# BatteryBalancingRev3.net
KiCad netlist of a schematic drawn in Altium Designer
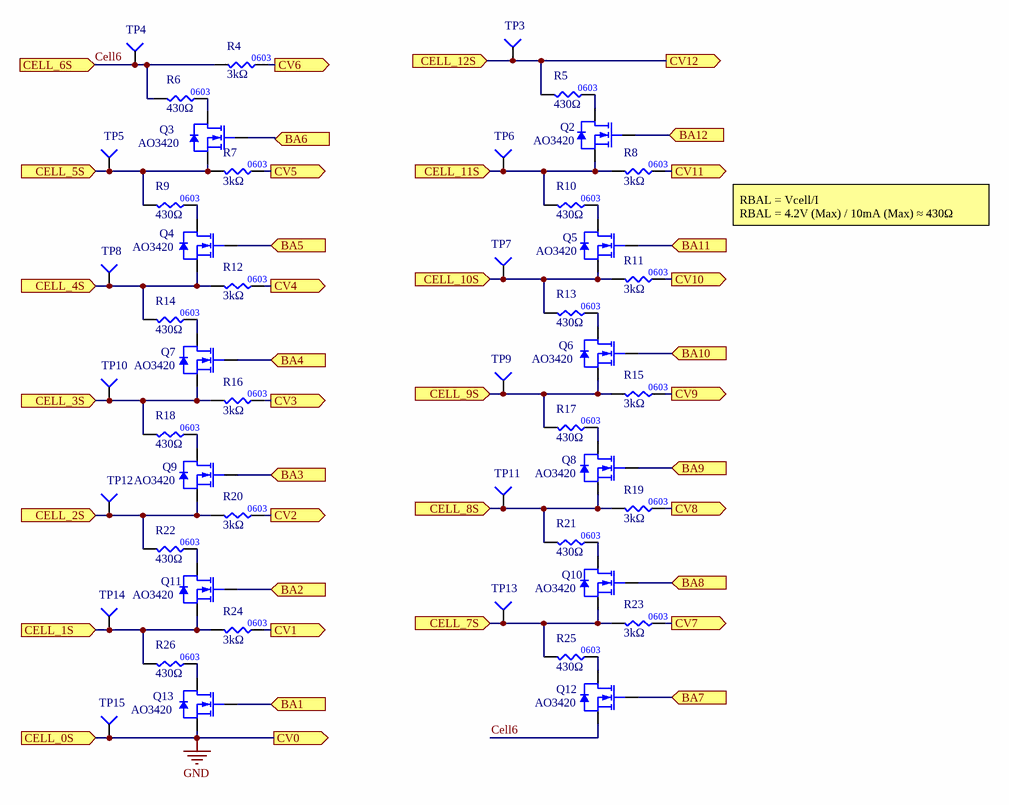
[diagram p0: BatteryBalancingRev3.SchDoc]

(export (version "E")
  (design (tool "Eeschema 10.0.6"))
  (components
    (comp (ref "Q2")
      (value "NMOS_20V_6A")
      (footprint "SOT23-3")
      (description "MOSFET N-CH 20V 6A SOT-23")
      (fields (field (name "MANUFACTURER PART NUMBER 1") "AO3420"))
      (libsource (lib "UWRT_Schematic_Library_2020") (part "NMOS_20V_6A"))
    )
    (comp (ref "Q3")
      (value "NMOS_20V_6A")
      (footprint "SOT23-3")
      (description "MOSFET N-CH 20V 6A SOT-23")
      (fields (field (name "MANUFACTURER PART NUMBER 1") "AO3420"))
      (libsource (lib "UWRT_Schematic_Library_2020") (part "NMOS_20V_6A"))
    )
    (comp (ref "Q4")
      (value "NMOS_20V_6A")
      (footprint "SOT23-3")
      (description "MOSFET N-CH 20V 6A SOT-23")
      (fields (field (name "MANUFACTURER PART NUMBER 1") "AO3420"))
      (libsource (lib "UWRT_Schematic_Library_2020") (part "NMOS_20V_6A"))
    )
    (comp (ref "Q5")
      (value "NMOS_20V_6A")
      (footprint "SOT23-3")
      (description "MOSFET N-CH 20V 6A SOT-23")
      (fields (field (name "MANUFACTURER PART NUMBER 1") "AO3420"))
      (libsource (lib "UWRT_Schematic_Library_2020") (part "NMOS_20V_6A"))
    )
    (comp (ref "Q6")
      (value "NMOS_20V_6A")
      (footprint "SOT23-3")
      (description "MOSFET N-CH 20V 6A SOT-23")
      (fields (field (name "MANUFACTURER PART NUMBER 1") "AO3420"))
      (libsource (lib "UWRT_Schematic_Library_2020") (part "NMOS_20V_6A"))
    )
    (comp (ref "Q7")
      (value "NMOS_20V_6A")
      (footprint "SOT23-3")
      (description "MOSFET N-CH 20V 6A SOT-23")
      (fields (field (name "MANUFACTURER PART NUMBER 1") "AO3420"))
      (libsource (lib "UWRT_Schematic_Library_2020") (part "NMOS_20V_6A"))
    )
    (comp (ref "Q8")
      (value "NMOS_20V_6A")
      (footprint "SOT23-3")
      (description "MOSFET N-CH 20V 6A SOT-23")
      (fields (field (name "MANUFACTURER PART NUMBER 1") "AO3420"))
      (libsource (lib "UWRT_Schematic_Library_2020") (part "NMOS_20V_6A"))
    )
    (comp (ref "Q9")
      (value "NMOS_20V_6A")
      (footprint "SOT23-3")
      (description "MOSFET N-CH 20V 6A SOT-23")
      (fields (field (name "MANUFACTURER PART NUMBER 1") "AO3420"))
      (libsource (lib "UWRT_Schematic_Library_2020") (part "NMOS_20V_6A"))
    )
    (comp (ref "Q10")
      (value "NMOS_20V_6A")
      (footprint "SOT23-3")
      (description "MOSFET N-CH 20V 6A SOT-23")
      (fields (field (name "MANUFACTURER PART NUMBER 1") "AO3420"))
      (libsource (lib "UWRT_Schematic_Library_2020") (part "NMOS_20V_6A"))
    )
    (comp (ref "Q11")
      (value "NMOS_20V_6A")
      (footprint "SOT23-3")
      (description "MOSFET N-CH 20V 6A SOT-23")
      (fields (field (name "MANUFACTURER PART NUMBER 1") "AO3420"))
      (libsource (lib "UWRT_Schematic_Library_2020") (part "NMOS_20V_6A"))
    )
    (comp (ref "Q12")
      (value "NMOS_20V_6A")
      (footprint "SOT23-3")
      (description "MOSFET N-CH 20V 6A SOT-23")
      (fields (field (name "MANUFACTURER PART NUMBER 1") "AO3420"))
      (libsource (lib "UWRT_Schematic_Library_2020") (part "NMOS_20V_6A"))
    )
    (comp (ref "Q13")
      (value "NMOS_20V_6A")
      (footprint "SOT23-3")
      (description "MOSFET N-CH 20V 6A SOT-23")
      (fields (field (name "MANUFACTURER PART NUMBER 1") "AO3420"))
      (libsource (lib "UWRT_Schematic_Library_2020") (part "NMOS_20V_6A"))
    )
    (comp (ref "R4")
      (value "3kΩ")
      (footprint "RES0603")
      (description "RES 3K OHM 1% 1/10W 0603")
      (fields (field (name "Comment") "RES_3kΩ_0603_1%"))
      (libsource (lib "UWRT_Schematic_Library_2020") (part "RES_3kΩ_0603_1%"))
    )
    (comp (ref "R5")
      (value "430Ω")
      (footprint "RES0603")
      (description "RES 430 OHM 5% 1/10W 0603")
      (fields (field (name "Comment") "RES_430Ω_0603_5%"))
      (libsource (lib "UWRT_Schematic_Library_2020") (part "RES_430Ω_0603_5%"))
    )
    (comp (ref "R6")
      (value "430Ω")
      (footprint "RES0603")
      (description "RES 430 OHM 5% 1/10W 0603")
      (fields (field (name "Comment") "RES_430Ω_0603_5%"))
      (libsource (lib "UWRT_Schematic_Library_2020") (part "RES_430Ω_0603_5%"))
    )
    (comp (ref "R7")
      (value "3kΩ")
      (footprint "RES0603")
      (description "RES 3K OHM 1% 1/10W 0603")
      (fields (field (name "Comment") "RES_3kΩ_0603_1%"))
      (libsource (lib "UWRT_Schematic_Library_2020") (part "RES_3kΩ_0603_1%"))
    )
    (comp (ref "R8")
      (value "3kΩ")
      (footprint "RES0603")
      (description "RES 3K OHM 1% 1/10W 0603")
      (fields (field (name "Comment") "RES_3kΩ_0603_1%"))
      (libsource (lib "UWRT_Schematic_Library_2020") (part "RES_3kΩ_0603_1%"))
    )
    (comp (ref "R9")
      (value "430Ω")
      (footprint "RES0603")
      (description "RES 430 OHM 5% 1/10W 0603")
      (fields (field (name "Comment") "RES_430Ω_0603_5%"))
      (libsource (lib "UWRT_Schematic_Library_2020") (part "RES_430Ω_0603_5%"))
    )
    (comp (ref "R10")
      (value "430Ω")
      (footprint "RES0603")
      (description "RES 430 OHM 5% 1/10W 0603")
      (fields (field (name "Comment") "RES_430Ω_0603_5%"))
      (libsource (lib "UWRT_Schematic_Library_2020") (part "RES_430Ω_0603_5%"))
    )
    (comp (ref "R11")
      (value "3kΩ")
      (footprint "RES0603")
      (description "RES 3K OHM 1% 1/10W 0603")
      (fields (field (name "Comment") "RES_3kΩ_0603_1%"))
      (libsource (lib "UWRT_Schematic_Library_2020") (part "RES_3kΩ_0603_1%"))
    )
    (comp (ref "R12")
      (value "3kΩ")
      (footprint "RES0603")
      (description "RES 3K OHM 1% 1/10W 0603")
      (fields (field (name "Comment") "RES_3kΩ_0603_1%"))
      (libsource (lib "UWRT_Schematic_Library_2020") (part "RES_3kΩ_0603_1%"))
    )
    (comp (ref "R13")
      (value "430Ω")
      (footprint "RES0603")
      (description "RES 430 OHM 5% 1/10W 0603")
      (fields (field (name "Comment") "RES_430Ω_0603_5%"))
      (libsource (lib "UWRT_Schematic_Library_2020") (part "RES_430Ω_0603_5%"))
    )
    (comp (ref "R14")
      (value "430Ω")
      (footprint "RES0603")
      (description "RES 430 OHM 5% 1/10W 0603")
      (fields (field (name "Comment") "RES_430Ω_0603_5%"))
      (libsource (lib "UWRT_Schematic_Library_2020") (part "RES_430Ω_0603_5%"))
    )
    (comp (ref "R15")
      (value "3kΩ")
      (footprint "RES0603")
      (description "RES 3K OHM 1% 1/10W 0603")
      (fields (field (name "Comment") "RES_3kΩ_0603_1%"))
      (libsource (lib "UWRT_Schematic_Library_2020") (part "RES_3kΩ_0603_1%"))
    )
    (comp (ref "R16")
      (value "3kΩ")
      (footprint "RES0603")
      (description "RES 3K OHM 1% 1/10W 0603")
      (fields (field (name "Comment") "RES_3kΩ_0603_1%"))
      (libsource (lib "UWRT_Schematic_Library_2020") (part "RES_3kΩ_0603_1%"))
    )
    (comp (ref "R17")
      (value "430Ω")
      (footprint "RES0603")
      (description "RES 430 OHM 5% 1/10W 0603")
      (fields (field (name "Comment") "RES_430Ω_0603_5%"))
      (libsource (lib "UWRT_Schematic_Library_2020") (part "RES_430Ω_0603_5%"))
    )
    (comp (ref "R18")
      (value "430Ω")
      (footprint "RES0603")
      (description "RES 430 OHM 5% 1/10W 0603")
      (fields (field (name "Comment") "RES_430Ω_0603_5%"))
      (libsource (lib "UWRT_Schematic_Library_2020") (part "RES_430Ω_0603_5%"))
    )
    (comp (ref "R19")
      (value "3kΩ")
      (footprint "RES0603")
      (description "RES 3K OHM 1% 1/10W 0603")
      (fields (field (name "Comment") "RES_3kΩ_0603_1%"))
      (libsource (lib "UWRT_Schematic_Library_2020") (part "RES_3kΩ_0603_1%"))
    )
    (comp (ref "R20")
      (value "3kΩ")
      (footprint "RES0603")
      (description "RES 3K OHM 1% 1/10W 0603")
      (fields (field (name "Comment") "RES_3kΩ_0603_1%"))
      (libsource (lib "UWRT_Schematic_Library_2020") (part "RES_3kΩ_0603_1%"))
    )
    (comp (ref "R21")
      (value "430Ω")
      (footprint "RES0603")
      (description "RES 430 OHM 5% 1/10W 0603")
      (fields (field (name "Comment") "RES_430Ω_0603_5%"))
      (libsource (lib "UWRT_Schematic_Library_2020") (part "RES_430Ω_0603_5%"))
    )
    (comp (ref "R22")
      (value "430Ω")
      (footprint "RES0603")
      (description "RES 430 OHM 5% 1/10W 0603")
      (fields (field (name "Comment") "RES_430Ω_0603_5%"))
      (libsource (lib "UWRT_Schematic_Library_2020") (part "RES_430Ω_0603_5%"))
    )
    (comp (ref "R23")
      (value "3kΩ")
      (footprint "RES0603")
      (description "RES 3K OHM 1% 1/10W 0603")
      (fields (field (name "Comment") "RES_3kΩ_0603_1%"))
      (libsource (lib "UWRT_Schematic_Library_2020") (part "RES_3kΩ_0603_1%"))
    )
    (comp (ref "R24")
      (value "3kΩ")
      (footprint "RES0603")
      (description "RES 3K OHM 1% 1/10W 0603")
      (fields (field (name "Comment") "RES_3kΩ_0603_1%"))
      (libsource (lib "UWRT_Schematic_Library_2020") (part "RES_3kΩ_0603_1%"))
    )
    (comp (ref "R25")
      (value "430Ω")
      (footprint "RES0603")
      (description "RES 430 OHM 5% 1/10W 0603")
      (fields (field (name "Comment") "RES_430Ω_0603_5%"))
      (libsource (lib "UWRT_Schematic_Library_2020") (part "RES_430Ω_0603_5%"))
    )
    (comp (ref "R26")
      (value "430Ω")
      (footprint "RES0603")
      (description "RES 430 OHM 5% 1/10W 0603")
      (fields (field (name "Comment") "RES_430Ω_0603_5%"))
      (libsource (lib "UWRT_Schematic_Library_2020") (part "RES_430Ω_0603_5%"))
    )
    (comp (ref "TP3")
      (value "TESTPOINT_1MM_SQUARE")
      (footprint "TESTPOINT_SQUARE_1MM")
      (description "CELL6")
      (libsource (lib "UWRT_Schematic_Library_2020") (part "TESTPOINT_1MM_SQUARE"))
    )
    (comp (ref "TP4")
      (value "TESTPOINT_1MM_SQUARE")
      (footprint "TESTPOINT_SQUARE_1MM")
      (description "CELL11")
      (libsource (lib "UWRT_Schematic_Library_2020") (part "TESTPOINT_1MM_SQUARE"))
    )
    (comp (ref "TP5")
      (value "TESTPOINT_1MM_SQUARE")
      (footprint "TESTPOINT_SQUARE_1MM")
      (description "CELL5")
      (libsource (lib "UWRT_Schematic_Library_2020") (part "TESTPOINT_1MM_SQUARE"))
    )
    (comp (ref "TP6")
      (value "TESTPOINT_1MM_SQUARE")
      (footprint "TESTPOINT_SQUARE_1MM")
      (description "CELL11")
      (libsource (lib "UWRT_Schematic_Library_2020") (part "TESTPOINT_1MM_SQUARE"))
    )
    (comp (ref "TP7")
      (value "TESTPOINT_1MM_SQUARE")
      (footprint "TESTPOINT_SQUARE_1MM")
      (description "CELL10")
      (libsource (lib "UWRT_Schematic_Library_2020") (part "TESTPOINT_1MM_SQUARE"))
    )
    (comp (ref "TP8")
      (value "TESTPOINT_1MM_SQUARE")
      (footprint "TESTPOINT_SQUARE_1MM")
      (description "CELL4")
      (libsource (lib "UWRT_Schematic_Library_2020") (part "TESTPOINT_1MM_SQUARE"))
    )
    (comp (ref "TP9")
      (value "TESTPOINT_1MM_SQUARE")
      (footprint "TESTPOINT_SQUARE_1MM")
      (description "CELL9")
      (libsource (lib "UWRT_Schematic_Library_2020") (part "TESTPOINT_1MM_SQUARE"))
    )
    (comp (ref "TP10")
      (value "TESTPOINT_1MM_SQUARE")
      (footprint "TESTPOINT_SQUARE_1MM")
      (description "CELL3")
      (libsource (lib "UWRT_Schematic_Library_2020") (part "TESTPOINT_1MM_SQUARE"))
    )
    (comp (ref "TP11")
      (value "TESTPOINT_1MM_SQUARE")
      (footprint "TESTPOINT_SQUARE_1MM")
      (description "CELL8")
      (libsource (lib "UWRT_Schematic_Library_2020") (part "TESTPOINT_1MM_SQUARE"))
    )
    (comp (ref "TP12")
      (value "TESTPOINT_1MM_SQUARE")
      (footprint "TESTPOINT_SQUARE_1MM")
      (description "CELL2")
      (libsource (lib "UWRT_Schematic_Library_2020") (part "TESTPOINT_1MM_SQUARE"))
    )
    (comp (ref "TP13")
      (value "TESTPOINT_1MM_SQUARE")
      (footprint "TESTPOINT_SQUARE_1MM")
      (description "CELL7")
      (libsource (lib "UWRT_Schematic_Library_2020") (part "TESTPOINT_1MM_SQUARE"))
    )
    (comp (ref "TP14")
      (value "TESTPOINT_1MM_SQUARE")
      (footprint "TESTPOINT_SQUARE_1MM")
      (description "CELL1")
      (libsource (lib "UWRT_Schematic_Library_2020") (part "TESTPOINT_1MM_SQUARE"))
    )
    (comp (ref "TP15")
      (value "TESTPOINT_1MM_SQUARE")
      (footprint "TESTPOINT_SQUARE_1MM")
      (description "CELL0")
      (libsource (lib "UWRT_Schematic_Library_2020") (part "TESTPOINT_1MM_SQUARE"))
    )
  )
  (nets
    (net (code "1") (name "/BA1") (class "Default")
      (node (ref "Q13") (pin "1") (pinfunction "GATE_1") (pintype "passive"))
    )
    (net (code "2") (name "/BA2") (class "Default")
      (node (ref "Q11") (pin "1") (pinfunction "GATE_1") (pintype "passive"))
    )
    (net (code "3") (name "/BA3") (class "Default")
      (node (ref "Q9") (pin "1") (pinfunction "GATE_1") (pintype "passive"))
    )
    (net (code "4") (name "/BA4") (class "Default")
      (node (ref "Q7") (pin "1") (pinfunction "GATE_1") (pintype "passive"))
    )
    (net (code "5") (name "/BA5") (class "Default")
      (node (ref "Q4") (pin "1") (pinfunction "GATE_1") (pintype "passive"))
    )
    (net (code "6") (name "/BA6") (class "Default")
      (node (ref "Q3") (pin "1") (pinfunction "GATE_1") (pintype "passive"))
    )
    (net (code "7") (name "/BA7") (class "Default")
      (node (ref "Q12") (pin "1") (pinfunction "GATE_1") (pintype "passive"))
    )
    (net (code "8") (name "/BA8") (class "Default")
      (node (ref "Q10") (pin "1") (pinfunction "GATE_1") (pintype "passive"))
    )
    (net (code "9") (name "/BA9") (class "Default")
      (node (ref "Q8") (pin "1") (pinfunction "GATE_1") (pintype "passive"))
    )
    (net (code "10") (name "/BA10") (class "Default")
      (node (ref "Q6") (pin "1") (pinfunction "GATE_1") (pintype "passive"))
    )
    (net (code "11") (name "/BA11") (class "Default")
      (node (ref "Q5") (pin "1") (pinfunction "GATE_1") (pintype "passive"))
    )
    (net (code "12") (name "/BA12") (class "Default")
      (node (ref "Q2") (pin "1") (pinfunction "GATE_1") (pintype "passive"))
    )
    (net (code "13") (name "/CELL_1S") (class "Default")
      (node (ref "Q11") (pin "2") (pinfunction "SOURCE_2") (pintype "passive"))
      (node (ref "R24") (pin "1") (pinfunction "1_1") (pintype "passive"))
      (node (ref "R26") (pin "1") (pinfunction "1_1") (pintype "passive"))
      (node (ref "TP14") (pin "1") (pinfunction "=value_1") (pintype "passive"))
    )
    (net (code "14") (name "/CELL_2S") (class "Default")
      (node (ref "Q9") (pin "2") (pinfunction "SOURCE_2") (pintype "passive"))
      (node (ref "R20") (pin "1") (pinfunction "1_1") (pintype "passive"))
      (node (ref "R22") (pin "1") (pinfunction "1_1") (pintype "passive"))
      (node (ref "TP12") (pin "1") (pinfunction "=value_1") (pintype "passive"))
    )
    (net (code "15") (name "/CELL_3S") (class "Default")
      (node (ref "Q7") (pin "2") (pinfunction "SOURCE_2") (pintype "passive"))
      (node (ref "R16") (pin "1") (pinfunction "1_1") (pintype "passive"))
      (node (ref "R18") (pin "1") (pinfunction "1_1") (pintype "passive"))
      (node (ref "TP10") (pin "1") (pinfunction "=value_1") (pintype "passive"))
    )
    (net (code "16") (name "/CELL_4S") (class "Default")
      (node (ref "Q4") (pin "2") (pinfunction "SOURCE_2") (pintype "passive"))
      (node (ref "R12") (pin "1") (pinfunction "1_1") (pintype "passive"))
      (node (ref "R14") (pin "1") (pinfunction "1_1") (pintype "passive"))
      (node (ref "TP8") (pin "1") (pinfunction "=value_1") (pintype "passive"))
    )
    (net (code "17") (name "/CELL_5S") (class "Default")
      (node (ref "Q3") (pin "2") (pinfunction "SOURCE_2") (pintype "passive"))
      (node (ref "R7") (pin "1") (pinfunction "1_1") (pintype "passive"))
      (node (ref "R9") (pin "1") (pinfunction "1_1") (pintype "passive"))
      (node (ref "TP5") (pin "1") (pinfunction "=value_1") (pintype "passive"))
    )
    (net (code "18") (name "/CELL_7S") (class "Default")
      (node (ref "Q10") (pin "2") (pinfunction "SOURCE_2") (pintype "passive"))
      (node (ref "R23") (pin "1") (pinfunction "1_1") (pintype "passive"))
      (node (ref "R25") (pin "1") (pinfunction "1_1") (pintype "passive"))
      (node (ref "TP13") (pin "1") (pinfunction "=value_1") (pintype "passive"))
    )
    (net (code "19") (name "/CELL_8S") (class "Default")
      (node (ref "Q8") (pin "2") (pinfunction "SOURCE_2") (pintype "passive"))
      (node (ref "R19") (pin "1") (pinfunction "1_1") (pintype "passive"))
      (node (ref "R21") (pin "1") (pinfunction "1_1") (pintype "passive"))
      (node (ref "TP11") (pin "1") (pinfunction "=value_1") (pintype "passive"))
    )
    (net (code "20") (name "/CELL_9S") (class "Default")
      (node (ref "Q6") (pin "2") (pinfunction "SOURCE_2") (pintype "passive"))
      (node (ref "R15") (pin "1") (pinfunction "1_1") (pintype "passive"))
      (node (ref "R17") (pin "1") (pinfunction "1_1") (pintype "passive"))
      (node (ref "TP9") (pin "1") (pinfunction "=value_1") (pintype "passive"))
    )
    (net (code "21") (name "/CELL_10S") (class "Default")
      (node (ref "Q5") (pin "2") (pinfunction "SOURCE_2") (pintype "passive"))
      (node (ref "R11") (pin "1") (pinfunction "1_1") (pintype "passive"))
      (node (ref "R13") (pin "1") (pinfunction "1_1") (pintype "passive"))
      (node (ref "TP7") (pin "1") (pinfunction "=value_1") (pintype "passive"))
    )
    (net (code "22") (name "/CELL_11S") (class "Default")
      (node (ref "Q2") (pin "2") (pinfunction "SOURCE_2") (pintype "passive"))
      (node (ref "R10") (pin "1") (pinfunction "1_1") (pintype "passive"))
      (node (ref "R8") (pin "1") (pinfunction "1_1") (pintype "passive"))
      (node (ref "TP6") (pin "1") (pinfunction "=value_1") (pintype "passive"))
    )
    (net (code "23") (name "/CELL_12S") (class "Default")
      (node (ref "R5") (pin "1") (pinfunction "1_1") (pintype "passive"))
      (node (ref "TP3") (pin "1") (pinfunction "=value_1") (pintype "passive"))
    )
    (net (code "24") (name "/CV1") (class "Default")
      (node (ref "R24") (pin "2") (pinfunction "2_2") (pintype "passive"))
    )
    (net (code "25") (name "/CV2") (class "Default")
      (node (ref "R20") (pin "2") (pinfunction "2_2") (pintype "passive"))
    )
    (net (code "26") (name "/CV3") (class "Default")
      (node (ref "R16") (pin "2") (pinfunction "2_2") (pintype "passive"))
    )
    (net (code "27") (name "/CV4") (class "Default")
      (node (ref "R12") (pin "2") (pinfunction "2_2") (pintype "passive"))
    )
    (net (code "28") (name "/CV5") (class "Default")
      (node (ref "R7") (pin "2") (pinfunction "2_2") (pintype "passive"))
    )
    (net (code "29") (name "/CV6") (class "Default")
      (node (ref "R4") (pin "2") (pinfunction "2_2") (pintype "passive"))
    )
    (net (code "30") (name "/CV7") (class "Default")
      (node (ref "R23") (pin "2") (pinfunction "2_2") (pintype "passive"))
    )
    (net (code "31") (name "/CV8") (class "Default")
      (node (ref "R19") (pin "2") (pinfunction "2_2") (pintype "passive"))
    )
    (net (code "32") (name "/CV9") (class "Default")
      (node (ref "R15") (pin "2") (pinfunction "2_2") (pintype "passive"))
    )
    (net (code "33") (name "/CV10") (class "Default")
      (node (ref "R11") (pin "2") (pinfunction "2_2") (pintype "passive"))
    )
    (net (code "34") (name "/CV11") (class "Default")
      (node (ref "R8") (pin "2") (pinfunction "2_2") (pintype "passive"))
    )
    (net (code "35") (name "/Cell6") (class "Default")
      (node (ref "Q12") (pin "2") (pinfunction "SOURCE_2") (pintype "passive"))
      (node (ref "R4") (pin "1") (pinfunction "1_1") (pintype "passive"))
      (node (ref "R6") (pin "1") (pinfunction "1_1") (pintype "passive"))
      (node (ref "TP4") (pin "1") (pinfunction "=value_1") (pintype "passive"))
    )
    (net (code "36") (name "GND") (class "Default")
      (node (ref "Q13") (pin "2") (pinfunction "SOURCE_2") (pintype "passive"))
      (node (ref "TP15") (pin "1") (pinfunction "=value_1") (pintype "passive"))
    )
    (net (code "37") (name "Net-(Q2-DRAIN)") (class "Default")
      (node (ref "Q2") (pin "3") (pinfunction "DRAIN_3") (pintype "passive"))
      (node (ref "R5") (pin "2") (pinfunction "2_2") (pintype "passive"))
    )
    (net (code "38") (name "Net-(Q3-DRAIN)") (class "Default")
      (node (ref "Q3") (pin "3") (pinfunction "DRAIN_3") (pintype "passive"))
      (node (ref "R6") (pin "2") (pinfunction "2_2") (pintype "passive"))
    )
    (net (code "39") (name "Net-(Q4-DRAIN)") (class "Default")
      (node (ref "Q4") (pin "3") (pinfunction "DRAIN_3") (pintype "passive"))
      (node (ref "R9") (pin "2") (pinfunction "2_2") (pintype "passive"))
    )
    (net (code "40") (name "Net-(Q5-DRAIN)") (class "Default")
      (node (ref "Q5") (pin "3") (pinfunction "DRAIN_3") (pintype "passive"))
      (node (ref "R10") (pin "2") (pinfunction "2_2") (pintype "passive"))
    )
    (net (code "41") (name "Net-(Q6-DRAIN)") (class "Default")
      (node (ref "Q6") (pin "3") (pinfunction "DRAIN_3") (pintype "passive"))
      (node (ref "R13") (pin "2") (pinfunction "2_2") (pintype "passive"))
    )
    (net (code "42") (name "Net-(Q7-DRAIN)") (class "Default")
      (node (ref "Q7") (pin "3") (pinfunction "DRAIN_3") (pintype "passive"))
      (node (ref "R14") (pin "2") (pinfunction "2_2") (pintype "passive"))
    )
    (net (code "43") (name "Net-(Q8-DRAIN)") (class "Default")
      (node (ref "Q8") (pin "3") (pinfunction "DRAIN_3") (pintype "passive"))
      (node (ref "R17") (pin "2") (pinfunction "2_2") (pintype "passive"))
    )
    (net (code "44") (name "Net-(Q9-DRAIN)") (class "Default")
      (node (ref "Q9") (pin "3") (pinfunction "DRAIN_3") (pintype "passive"))
      (node (ref "R18") (pin "2") (pinfunction "2_2") (pintype "passive"))
    )
    (net (code "45") (name "Net-(Q10-DRAIN)") (class "Default")
      (node (ref "Q10") (pin "3") (pinfunction "DRAIN_3") (pintype "passive"))
      (node (ref "R21") (pin "2") (pinfunction "2_2") (pintype "passive"))
    )
    (net (code "46") (name "Net-(Q11-DRAIN)") (class "Default")
      (node (ref "Q11") (pin "3") (pinfunction "DRAIN_3") (pintype "passive"))
      (node (ref "R22") (pin "2") (pinfunction "2_2") (pintype "passive"))
    )
    (net (code "47") (name "Net-(Q12-DRAIN)") (class "Default")
      (node (ref "Q12") (pin "3") (pinfunction "DRAIN_3") (pintype "passive"))
      (node (ref "R25") (pin "2") (pinfunction "2_2") (pintype "passive"))
    )
    (net (code "48") (name "Net-(Q13-DRAIN)") (class "Default")
      (node (ref "Q13") (pin "3") (pinfunction "DRAIN_3") (pintype "passive"))
      (node (ref "R26") (pin "2") (pinfunction "2_2") (pintype "passive"))
    )
  )
)
